# comcon_version_av.net
KiCad netlist of a schematic drawn in EAGLE
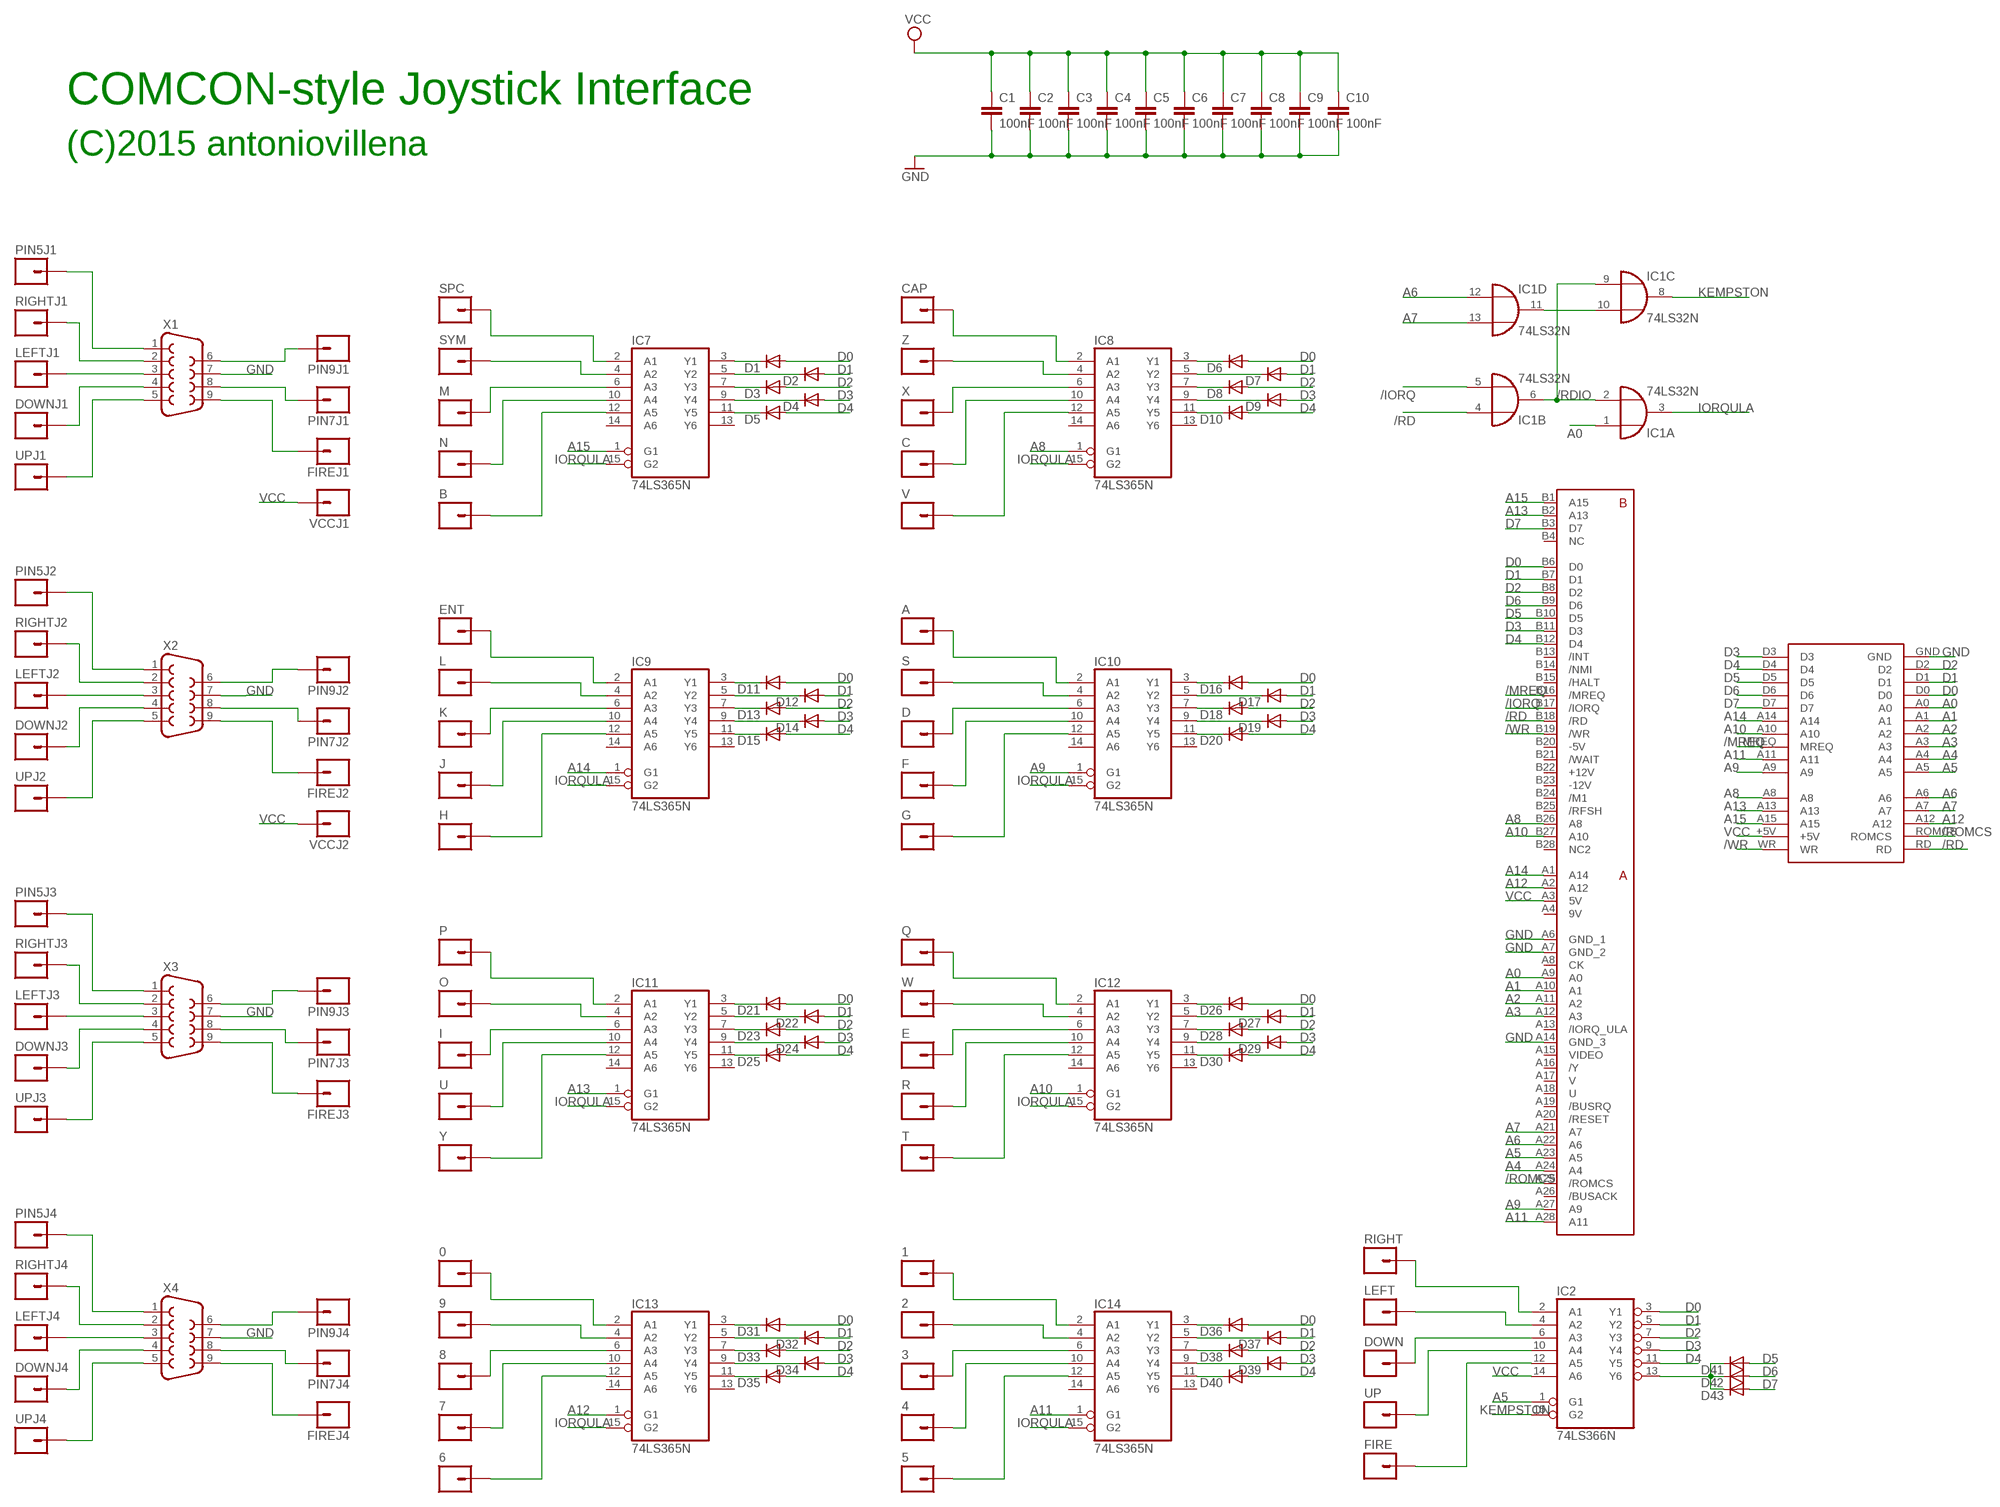
[diagram p0: schematic, sheet 1]

(export (version "E")
  (design (tool "Eeschema 10.0.6"))
  (components
    (comp (ref "0")
      (value "M01PTH")
      (footprint "eagle-import:1X01")
      (libsource (lib "eagle-import") (part "M01PTH"))
    )
    (comp (ref "1")
      (value "M01PTH")
      (footprint "eagle-import:1X01")
      (libsource (lib "eagle-import") (part "M01PTH"))
    )
    (comp (ref "2")
      (value "M01PTH")
      (footprint "eagle-import:1X01")
      (libsource (lib "eagle-import") (part "M01PTH"))
    )
    (comp (ref "3")
      (value "M01PTH")
      (footprint "eagle-import:1X01")
      (libsource (lib "eagle-import") (part "M01PTH"))
    )
    (comp (ref "4")
      (value "M01PTH")
      (footprint "eagle-import:1X01")
      (libsource (lib "eagle-import") (part "M01PTH"))
    )
    (comp (ref "5")
      (value "M01PTH")
      (footprint "eagle-import:1X01")
      (libsource (lib "eagle-import") (part "M01PTH"))
    )
    (comp (ref "6")
      (value "M01PTH")
      (footprint "eagle-import:1X01")
      (libsource (lib "eagle-import") (part "M01PTH"))
    )
    (comp (ref "7")
      (value "M01PTH")
      (footprint "eagle-import:1X01")
      (libsource (lib "eagle-import") (part "M01PTH"))
    )
    (comp (ref "8")
      (value "M01PTH")
      (footprint "eagle-import:1X01")
      (libsource (lib "eagle-import") (part "M01PTH"))
    )
    (comp (ref "9")
      (value "M01PTH")
      (footprint "eagle-import:1X01")
      (libsource (lib "eagle-import") (part "M01PTH"))
    )
    (comp (ref "A")
      (value "M01PTH")
      (footprint "eagle-import:1X01")
      (libsource (lib "eagle-import") (part "M01PTH"))
    )
    (comp (ref "B")
      (value "M01PTH")
      (footprint "eagle-import:1X01")
      (libsource (lib "eagle-import") (part "M01PTH"))
    )
    (comp (ref "C")
      (value "M01PTH")
      (footprint "eagle-import:1X01")
      (libsource (lib "eagle-import") (part "M01PTH"))
    )
    (comp (ref "C1")
      (value "100nF")
      (footprint "eagle-import:C050-025X075")
      (libsource (lib "eagle-import") (part "C-EU050-025X075"))
    )
    (comp (ref "C2")
      (value "100nF")
      (footprint "eagle-import:C050-025X075")
      (libsource (lib "eagle-import") (part "C-EU050-025X075"))
    )
    (comp (ref "C3")
      (value "100nF")
      (footprint "eagle-import:C050-025X075")
      (libsource (lib "eagle-import") (part "C-EU050-025X075"))
    )
    (comp (ref "C4")
      (value "100nF")
      (footprint "eagle-import:C050-025X075")
      (libsource (lib "eagle-import") (part "C-EU050-025X075"))
    )
    (comp (ref "C5")
      (value "100nF")
      (footprint "eagle-import:C050-025X075")
      (libsource (lib "eagle-import") (part "C-EU050-025X075"))
    )
    (comp (ref "C6")
      (value "100nF")
      (footprint "eagle-import:C050-025X075")
      (libsource (lib "eagle-import") (part "C-EU050-025X075"))
    )
    (comp (ref "C7")
      (value "100nF")
      (footprint "eagle-import:C050-025X075")
      (libsource (lib "eagle-import") (part "C-EU050-025X075"))
    )
    (comp (ref "C8")
      (value "100nF")
      (footprint "eagle-import:C050-025X075")
      (libsource (lib "eagle-import") (part "C-EU050-025X075"))
    )
    (comp (ref "C9")
      (value "100nF")
      (footprint "eagle-import:C050-025X075")
      (libsource (lib "eagle-import") (part "C-EU050-025X075"))
    )
    (comp (ref "C10")
      (value "100nF")
      (footprint "eagle-import:C050-025X075")
      (libsource (lib "eagle-import") (part "C-EU050-025X075"))
    )
    (comp (ref "CAP")
      (value "M01PTH")
      (footprint "eagle-import:1X01")
      (libsource (lib "eagle-import") (part "M01PTH"))
    )
    (comp (ref "D")
      (value "M01PTH")
      (footprint "eagle-import:1X01")
      (libsource (lib "eagle-import") (part "M01PTH"))
    )
    (comp (ref "D1")
      (value "1N4148DO35-7")
      (footprint "eagle-import:DO35-7")
      (libsource (lib "eagle-import") (part "1N4148DO35-7"))
    )
    (comp (ref "D2")
      (value "1N4148DO35-7")
      (footprint "eagle-import:DO35-7")
      (libsource (lib "eagle-import") (part "1N4148DO35-7"))
    )
    (comp (ref "D3")
      (value "1N4148DO35-7")
      (footprint "eagle-import:DO35-7")
      (libsource (lib "eagle-import") (part "1N4148DO35-7"))
    )
    (comp (ref "D4")
      (value "1N4148DO35-7")
      (footprint "eagle-import:DO35-7")
      (libsource (lib "eagle-import") (part "1N4148DO35-7"))
    )
    (comp (ref "D5")
      (value "1N4148DO35-7")
      (footprint "eagle-import:DO35-7")
      (libsource (lib "eagle-import") (part "1N4148DO35-7"))
    )
    (comp (ref "D6")
      (value "1N4148DO35-7")
      (footprint "eagle-import:DO35-7")
      (libsource (lib "eagle-import") (part "1N4148DO35-7"))
    )
    (comp (ref "D7")
      (value "1N4148DO35-7")
      (footprint "eagle-import:DO35-7")
      (libsource (lib "eagle-import") (part "1N4148DO35-7"))
    )
    (comp (ref "D8")
      (value "1N4148DO35-7")
      (footprint "eagle-import:DO35-7")
      (libsource (lib "eagle-import") (part "1N4148DO35-7"))
    )
    (comp (ref "D9")
      (value "1N4148DO35-7")
      (footprint "eagle-import:DO35-7")
      (libsource (lib "eagle-import") (part "1N4148DO35-7"))
    )
    (comp (ref "D10")
      (value "1N4148DO35-7")
      (footprint "eagle-import:DO35-7")
      (libsource (lib "eagle-import") (part "1N4148DO35-7"))
    )
    (comp (ref "D11")
      (value "1N4148DO35-7")
      (footprint "eagle-import:DO35-7")
      (libsource (lib "eagle-import") (part "1N4148DO35-7"))
    )
    (comp (ref "D12")
      (value "1N4148DO35-7")
      (footprint "eagle-import:DO35-7")
      (libsource (lib "eagle-import") (part "1N4148DO35-7"))
    )
    (comp (ref "D13")
      (value "1N4148DO35-7")
      (footprint "eagle-import:DO35-7")
      (libsource (lib "eagle-import") (part "1N4148DO35-7"))
    )
    (comp (ref "D14")
      (value "1N4148DO35-7")
      (footprint "eagle-import:DO35-7")
      (libsource (lib "eagle-import") (part "1N4148DO35-7"))
    )
    (comp (ref "D15")
      (value "1N4148DO35-7")
      (footprint "eagle-import:DO35-7")
      (libsource (lib "eagle-import") (part "1N4148DO35-7"))
    )
    (comp (ref "D16")
      (value "1N4148DO35-7")
      (footprint "eagle-import:DO35-7")
      (libsource (lib "eagle-import") (part "1N4148DO35-7"))
    )
    (comp (ref "D17")
      (value "1N4148DO35-7")
      (footprint "eagle-import:DO35-7")
      (libsource (lib "eagle-import") (part "1N4148DO35-7"))
    )
    (comp (ref "D18")
      (value "1N4148DO35-7")
      (footprint "eagle-import:DO35-7")
      (libsource (lib "eagle-import") (part "1N4148DO35-7"))
    )
    (comp (ref "D19")
      (value "1N4148DO35-7")
      (footprint "eagle-import:DO35-7")
      (libsource (lib "eagle-import") (part "1N4148DO35-7"))
    )
    (comp (ref "D20")
      (value "1N4148DO35-7")
      (footprint "eagle-import:DO35-7")
      (libsource (lib "eagle-import") (part "1N4148DO35-7"))
    )
    (comp (ref "D21")
      (value "1N4148DO35-7")
      (footprint "eagle-import:DO35-7")
      (libsource (lib "eagle-import") (part "1N4148DO35-7"))
    )
    (comp (ref "D22")
      (value "1N4148DO35-7")
      (footprint "eagle-import:DO35-7")
      (libsource (lib "eagle-import") (part "1N4148DO35-7"))
    )
    (comp (ref "D23")
      (value "1N4148DO35-7")
      (footprint "eagle-import:DO35-7")
      (libsource (lib "eagle-import") (part "1N4148DO35-7"))
    )
    (comp (ref "D24")
      (value "1N4148DO35-7")
      (footprint "eagle-import:DO35-7")
      (libsource (lib "eagle-import") (part "1N4148DO35-7"))
    )
    (comp (ref "D25")
      (value "1N4148DO35-7")
      (footprint "eagle-import:DO35-7")
      (libsource (lib "eagle-import") (part "1N4148DO35-7"))
    )
    (comp (ref "D26")
      (value "1N4148DO35-7")
      (footprint "eagle-import:DO35-7")
      (libsource (lib "eagle-import") (part "1N4148DO35-7"))
    )
    (comp (ref "D27")
      (value "1N4148DO35-7")
      (footprint "eagle-import:DO35-7")
      (libsource (lib "eagle-import") (part "1N4148DO35-7"))
    )
    (comp (ref "D28")
      (value "1N4148DO35-7")
      (footprint "eagle-import:DO35-7")
      (libsource (lib "eagle-import") (part "1N4148DO35-7"))
    )
    (comp (ref "D29")
      (value "1N4148DO35-7")
      (footprint "eagle-import:DO35-7")
      (libsource (lib "eagle-import") (part "1N4148DO35-7"))
    )
    (comp (ref "D30")
      (value "1N4148DO35-7")
      (footprint "eagle-import:DO35-7")
      (libsource (lib "eagle-import") (part "1N4148DO35-7"))
    )
    (comp (ref "D31")
      (value "1N4148DO35-7")
      (footprint "eagle-import:DO35-7")
      (libsource (lib "eagle-import") (part "1N4148DO35-7"))
    )
    (comp (ref "D32")
      (value "1N4148DO35-7")
      (footprint "eagle-import:DO35-7")
      (libsource (lib "eagle-import") (part "1N4148DO35-7"))
    )
    (comp (ref "D33")
      (value "1N4148DO35-7")
      (footprint "eagle-import:DO35-7")
      (libsource (lib "eagle-import") (part "1N4148DO35-7"))
    )
    (comp (ref "D34")
      (value "1N4148DO35-7")
      (footprint "eagle-import:DO35-7")
      (libsource (lib "eagle-import") (part "1N4148DO35-7"))
    )
    (comp (ref "D35")
      (value "1N4148DO35-7")
      (footprint "eagle-import:DO35-7")
      (libsource (lib "eagle-import") (part "1N4148DO35-7"))
    )
    (comp (ref "D36")
      (value "1N4148DO35-7")
      (footprint "eagle-import:DO35-7")
      (libsource (lib "eagle-import") (part "1N4148DO35-7"))
    )
    (comp (ref "D37")
      (value "1N4148DO35-7")
      (footprint "eagle-import:DO35-7")
      (libsource (lib "eagle-import") (part "1N4148DO35-7"))
    )
    (comp (ref "D38")
      (value "1N4148DO35-7")
      (footprint "eagle-import:DO35-7")
      (libsource (lib "eagle-import") (part "1N4148DO35-7"))
    )
    (comp (ref "D39")
      (value "1N4148DO35-7")
      (footprint "eagle-import:DO35-7")
      (libsource (lib "eagle-import") (part "1N4148DO35-7"))
    )
    (comp (ref "D40")
      (value "1N4148DO35-7")
      (footprint "eagle-import:DO35-7")
      (libsource (lib "eagle-import") (part "1N4148DO35-7"))
    )
    (comp (ref "D41")
      (value "1N4148DO35-10")
      (footprint "eagle-import:DO35-10")
      (libsource (lib "eagle-import") (part "1N4148DO35-10"))
    )
    (comp (ref "D42")
      (value "1N4148DO35-10")
      (footprint "eagle-import:DO35-10")
      (libsource (lib "eagle-import") (part "1N4148DO35-10"))
    )
    (comp (ref "D43")
      (value "1N4148DO35-7")
      (footprint "eagle-import:DO35-7")
      (libsource (lib "eagle-import") (part "1N4148DO35-7"))
    )
    (comp (ref "DOWN")
      (value "M01PTH")
      (footprint "eagle-import:1X01")
      (libsource (lib "eagle-import") (part "M01PTH"))
    )
    (comp (ref "DOWNJ1")
      (value "M01PTH")
      (footprint "eagle-import:1X01")
      (libsource (lib "eagle-import") (part "M01PTH"))
    )
    (comp (ref "DOWNJ2")
      (value "M01PTH")
      (footprint "eagle-import:1X01")
      (libsource (lib "eagle-import") (part "M01PTH"))
    )
    (comp (ref "DOWNJ3")
      (value "M01PTH")
      (footprint "eagle-import:1X01")
      (libsource (lib "eagle-import") (part "M01PTH"))
    )
    (comp (ref "DOWNJ4")
      (value "M01PTH")
      (footprint "eagle-import:1X01")
      (libsource (lib "eagle-import") (part "M01PTH"))
    )
    (comp (ref "E")
      (value "M01PTH")
      (footprint "eagle-import:1X01")
      (libsource (lib "eagle-import") (part "M01PTH"))
    )
    (comp (ref "ENT")
      (value "M01PTH")
      (footprint "eagle-import:1X01")
      (libsource (lib "eagle-import") (part "M01PTH"))
    )
    (comp (ref "F")
      (value "M01PTH")
      (footprint "eagle-import:1X01")
      (libsource (lib "eagle-import") (part "M01PTH"))
    )
    (comp (ref "FIRE")
      (value "M01PTH")
      (footprint "eagle-import:1X01")
      (libsource (lib "eagle-import") (part "M01PTH"))
    )
    (comp (ref "FIREJ1")
      (value "M01PTH")
      (footprint "eagle-import:1X01")
      (libsource (lib "eagle-import") (part "M01PTH"))
    )
    (comp (ref "FIREJ2")
      (value "M01PTH")
      (footprint "eagle-import:1X01")
      (libsource (lib "eagle-import") (part "M01PTH"))
    )
    (comp (ref "FIREJ3")
      (value "M01PTH")
      (footprint "eagle-import:1X01")
      (libsource (lib "eagle-import") (part "M01PTH"))
    )
    (comp (ref "FIREJ4")
      (value "M01PTH")
      (footprint "eagle-import:1X01")
      (libsource (lib "eagle-import") (part "M01PTH"))
    )
    (comp (ref "G")
      (value "M01PTH")
      (footprint "eagle-import:1X01")
      (libsource (lib "eagle-import") (part "M01PTH"))
    )
    (comp (ref "H")
      (value "M01PTH")
      (footprint "eagle-import:1X01")
      (libsource (lib "eagle-import") (part "M01PTH"))
    )
    (comp (ref "I")
      (value "M01PTH")
      (footprint "eagle-import:1X01")
      (libsource (lib "eagle-import") (part "M01PTH"))
    )
    (comp (ref "IC1")
      (value "74LS32N")
      (footprint "eagle-import:DIL14")
      (libsource (lib "eagle-import") (part "7432NLS"))
    )
    (comp (ref "IC2")
      (value "74LS366N")
      (footprint "eagle-import:DIL16")
      (libsource (lib "eagle-import") (part "74366NLS"))
    )
    (comp (ref "IC7")
      (value "74LS365N")
      (footprint "eagle-import:DIL16")
      (libsource (lib "eagle-import") (part "74365NHC"))
    )
    (comp (ref "IC8")
      (value "74LS365N")
      (footprint "eagle-import:DIL16")
      (libsource (lib "eagle-import") (part "74365NHC"))
    )
    (comp (ref "IC9")
      (value "74LS365N")
      (footprint "eagle-import:DIL16")
      (libsource (lib "eagle-import") (part "74365NHC"))
    )
    (comp (ref "IC10")
      (value "74LS365N")
      (footprint "eagle-import:DIL16")
      (libsource (lib "eagle-import") (part "74365NHC"))
    )
    (comp (ref "IC11")
      (value "74LS365N")
      (footprint "eagle-import:DIL16")
      (libsource (lib "eagle-import") (part "74365NHC"))
    )
    (comp (ref "IC12")
      (value "74LS365N")
      (footprint "eagle-import:DIL16")
      (libsource (lib "eagle-import") (part "74365NHC"))
    )
    (comp (ref "IC13")
      (value "74LS365N")
      (footprint "eagle-import:DIL16")
      (libsource (lib "eagle-import") (part "74365NHC"))
    )
    (comp (ref "IC14")
      (value "74LS365N")
      (footprint "eagle-import:DIL16")
      (libsource (lib "eagle-import") (part "74365NHC"))
    )
    (comp (ref "J")
      (value "M01PTH")
      (footprint "eagle-import:1X01")
      (libsource (lib "eagle-import") (part "M01PTH"))
    )
    (comp (ref "K")
      (value "M01PTH")
      (footprint "eagle-import:1X01")
      (libsource (lib "eagle-import") (part "M01PTH"))
    )
    (comp (ref "L")
      (value "M01PTH")
      (footprint "eagle-import:1X01")
      (libsource (lib "eagle-import") (part "M01PTH"))
    )
    (comp (ref "LEFT")
      (value "M01PTH")
      (footprint "eagle-import:1X01")
      (libsource (lib "eagle-import") (part "M01PTH"))
    )
    (comp (ref "LEFTJ1")
      (value "M01PTH")
      (footprint "eagle-import:1X01")
      (libsource (lib "eagle-import") (part "M01PTH"))
    )
    (comp (ref "LEFTJ2")
      (value "M01PTH")
      (footprint "eagle-import:1X01")
      (libsource (lib "eagle-import") (part "M01PTH"))
    )
    (comp (ref "LEFTJ3")
      (value "M01PTH")
      (footprint "eagle-import:1X01")
      (libsource (lib "eagle-import") (part "M01PTH"))
    )
    (comp (ref "LEFTJ4")
      (value "M01PTH")
      (footprint "eagle-import:1X01")
      (libsource (lib "eagle-import") (part "M01PTH"))
    )
    (comp (ref "M")
      (value "M01PTH")
      (footprint "eagle-import:1X01")
      (libsource (lib "eagle-import") (part "M01PTH"))
    )
    (comp (ref "N")
      (value "M01PTH")
      (footprint "eagle-import:1X01")
      (libsource (lib "eagle-import") (part "M01PTH"))
    )
    (comp (ref "O")
      (value "M01PTH")
      (footprint "eagle-import:1X01")
      (libsource (lib "eagle-import") (part "M01PTH"))
    )
    (comp (ref "P")
      (value "M01PTH")
      (footprint "eagle-import:1X01")
      (libsource (lib "eagle-import") (part "M01PTH"))
    )
    (comp (ref "PIN5J1")
      (value "M01PTH")
      (footprint "eagle-import:1X01")
      (libsource (lib "eagle-import") (part "M01PTH"))
    )
    (comp (ref "PIN5J2")
      (value "M01PTH")
      (footprint "eagle-import:1X01")
      (libsource (lib "eagle-import") (part "M01PTH"))
    )
    (comp (ref "PIN5J3")
      (value "M01PTH")
      (footprint "eagle-import:1X01")
      (libsource (lib "eagle-import") (part "M01PTH"))
    )
    (comp (ref "PIN5J4")
      (value "M01PTH")
      (footprint "eagle-import:1X01")
      (libsource (lib "eagle-import") (part "M01PTH"))
    )
    (comp (ref "PIN7J1")
      (value "M01PTH")
      (footprint "eagle-import:1X01")
      (libsource (lib "eagle-import") (part "M01PTH"))
    )
    (comp (ref "PIN7J2")
      (value "M01PTH")
      (footprint "eagle-import:1X01")
      (libsource (lib "eagle-import") (part "M01PTH"))
    )
    (comp (ref "PIN7J3")
      (value "M01PTH")
      (footprint "eagle-import:1X01")
      (libsource (lib "eagle-import") (part "M01PTH"))
    )
    (comp (ref "PIN7J4")
      (value "M01PTH")
      (footprint "eagle-import:1X01")
      (libsource (lib "eagle-import") (part "M01PTH"))
    )
    (comp (ref "PIN9J1")
      (value "M01PTH")
      (footprint "eagle-import:1X01")
      (libsource (lib "eagle-import") (part "M01PTH"))
    )
    (comp (ref "PIN9J2")
      (value "M01PTH")
      (footprint "eagle-import:1X01")
      (libsource (lib "eagle-import") (part "M01PTH"))
    )
    (comp (ref "PIN9J3")
      (value "M01PTH")
      (footprint "eagle-import:1X01")
      (libsource (lib "eagle-import") (part "M01PTH"))
    )
    (comp (ref "PIN9J4")
      (value "M01PTH")
      (footprint "eagle-import:1X01")
      (libsource (lib "eagle-import") (part "M01PTH"))
    )
    (comp (ref "Q")
      (value "M01PTH")
      (footprint "eagle-import:1X01")
      (libsource (lib "eagle-import") (part "M01PTH"))
    )
    (comp (ref "R")
      (value "M01PTH")
      (footprint "eagle-import:1X01")
      (libsource (lib "eagle-import") (part "M01PTH"))
    )
    (comp (ref "RIGHT")
      (value "M01PTH")
      (footprint "eagle-import:1X01")
      (libsource (lib "eagle-import") (part "M01PTH"))
    )
    (comp (ref "RIGHTJ1")
      (value "M01PTH")
      (footprint "eagle-import:1X01")
      (libsource (lib "eagle-import") (part "M01PTH"))
    )
    (comp (ref "RIGHTJ2")
      (value "M01PTH")
      (footprint "eagle-import:1X01")
      (libsource (lib "eagle-import") (part "M01PTH"))
    )
    (comp (ref "RIGHTJ3")
      (value "M01PTH")
      (footprint "eagle-import:1X01")
      (libsource (lib "eagle-import") (part "M01PTH"))
    )
    (comp (ref "RIGHTJ4")
      (value "M01PTH")
      (footprint "eagle-import:1X01")
      (libsource (lib "eagle-import") (part "M01PTH"))
    )
    (comp (ref "S")
      (value "M01PTH")
      (footprint "eagle-import:1X01")
      (libsource (lib "eagle-import") (part "M01PTH"))
    )
    (comp (ref "SPC")
      (value "M01PTH")
      (footprint "eagle-import:1X01")
      (libsource (lib "eagle-import") (part "M01PTH"))
    )
    (comp (ref "SYM")
      (value "M01PTH")
      (footprint "eagle-import:1X01")
      (libsource (lib "eagle-import") (part "M01PTH"))
    )
    (comp (ref "T")
      (value "M01PTH")
      (footprint "eagle-import:1X01")
      (libsource (lib "eagle-import") (part "M01PTH"))
    )
    (comp (ref "U")
      (value "M01PTH")
      (footprint "eagle-import:1X01")
      (libsource (lib "eagle-import") (part "M01PTH"))
    )
    (comp (ref "U$1")
      (value "ZX_CARTRIDGE")
      (footprint "eagle-import:ZX_CARTRIDGE")
      (libsource (lib "eagle-import") (part "ZX_CARTRIDGE"))
    )
    (comp (ref "U$3")
      (value "ZXSP_ED2X28_SPE")
      (footprint "eagle-import:2X28_SPE")
      (libsource (lib "eagle-import") (part "ZXSP_ED2X28_SPE"))
    )
    (comp (ref "UP")
      (value "M01PTH")
      (footprint "eagle-import:1X01")
      (libsource (lib "eagle-import") (part "M01PTH"))
    )
    (comp (ref "UPJ1")
      (value "M01PTH")
      (footprint "eagle-import:1X01")
      (libsource (lib "eagle-import") (part "M01PTH"))
    )
    (comp (ref "UPJ2")
      (value "M01PTH")
      (footprint "eagle-import:1X01")
      (libsource (lib "eagle-import") (part "M01PTH"))
    )
    (comp (ref "UPJ3")
      (value "M01PTH")
      (footprint "eagle-import:1X01")
      (libsource (lib "eagle-import") (part "M01PTH"))
    )
    (comp (ref "UPJ4")
      (value "M01PTH")
      (footprint "eagle-import:1X01")
      (libsource (lib "eagle-import") (part "M01PTH"))
    )
    (comp (ref "V")
      (value "M01PTH")
      (footprint "eagle-import:1X01")
      (libsource (lib "eagle-import") (part "M01PTH"))
    )
    (comp (ref "VCCJ1")
      (value "M01PTH")
      (footprint "eagle-import:1X01")
      (libsource (lib "eagle-import") (part "M01PTH"))
    )
    (comp (ref "VCCJ2")
      (value "M01PTH")
      (footprint "eagle-import:1X01")
      (libsource (lib "eagle-import") (part "M01PTH"))
    )
    (comp (ref "W")
      (value "M01PTH")
      (footprint "eagle-import:1X01")
      (libsource (lib "eagle-import") (part "M01PTH"))
    )
    (comp (ref "X")
      (value "M01PTH")
      (footprint "eagle-import:1X01")
      (libsource (lib "eagle-import") (part "M01PTH"))
    )
    (comp (ref "X1")
      (value "F09D")
      (footprint "eagle-import:F09D")
      (libsource (lib "eagle-import") (part "F09D"))
    )
    (comp (ref "X2")
      (value "F09D")
      (footprint "eagle-import:F09D")
      (libsource (lib "eagle-import") (part "F09D"))
    )
    (comp (ref "X3")
      (value "F09D")
      (footprint "eagle-import:F09D")
      (libsource (lib "eagle-import") (part "F09D"))
    )
    (comp (ref "X4")
      (value "F09D")
      (footprint "eagle-import:F09D")
      (libsource (lib "eagle-import") (part "F09D"))
    )
    (comp (ref "Y")
      (value "M01PTH")
      (footprint "eagle-import:1X01")
      (libsource (lib "eagle-import") (part "M01PTH"))
    )
    (comp (ref "Z")
      (value "M01PTH")
      (footprint "eagle-import:1X01")
      (libsource (lib "eagle-import") (part "M01PTH"))
    )
  )
  (nets
    (net (code "1") (name "/+12V") (class "Default")
      (node (ref "U$3") (pin "B22") (pinfunction "+12V_B22") (pintype "power_in"))
    )
    (net (code "2") (name "/-5V") (class "Default")
      (node (ref "U$3") (pin "B20") (pinfunction "-5V_B20") (pintype "power_in"))
    )
    (net (code "3") (name "/-12V") (class "Default")
      (node (ref "U$3") (pin "B23") (pinfunction "-12V_B23") (pintype "power_in"))
    )
    (net (code "4") (name "/9V") (class "Default")
      (node (ref "U$3") (pin "A4") (pinfunction "9V_A4") (pintype "power_in"))
    )
    (net (code "5") (name "/A0") (class "Default")
      (node (ref "IC1") (pin "1") (pinfunction "I0_1") (pintype "input"))
      (node (ref "U$1") (pin "A0") (pinfunction "A0_A0") (pintype "bidirectional"))
      (node (ref "U$3") (pin "A9") (pinfunction "A0_A9") (pintype "bidirectional"))
    )
    (net (code "6") (name "/A1") (class "Default")
      (node (ref "U$1") (pin "A1") (pinfunction "A1_A1") (pintype "bidirectional"))
      (node (ref "U$3") (pin "A10") (pinfunction "A1_A10") (pintype "bidirectional"))
    )
    (net (code "7") (name "/A2") (class "Default")
      (node (ref "U$1") (pin "A2") (pinfunction "A2_A2") (pintype "bidirectional"))
      (node (ref "U$3") (pin "A11") (pinfunction "A2_A11") (pintype "bidirectional"))
    )
    (net (code "8") (name "/A3") (class "Default")
      (node (ref "U$1") (pin "A3") (pinfunction "A3_A3") (pintype "bidirectional"))
      (node (ref "U$3") (pin "A12") (pinfunction "A3_A12") (pintype "bidirectional"))
    )
    (net (code "9") (name "/A4") (class "Default")
      (node (ref "U$1") (pin "A4") (pinfunction "A4_A4") (pintype "bidirectional"))
      (node (ref "U$3") (pin "A24") (pinfunction "A4_A24") (pintype "bidirectional"))
    )
    (net (code "10") (name "/A5") (class "Default")
      (node (ref "IC2") (pin "1") (pinfunction "G1_1") (pintype "input"))
      (node (ref "U$1") (pin "A5") (pinfunction "A5_A5") (pintype "bidirectional"))
      (node (ref "U$3") (pin "A23") (pinfunction "A5_A23") (pintype "bidirectional"))
    )
    (net (code "11") (name "/A6") (class "Default")
      (node (ref "IC1") (pin "12") (pinfunction "I0_12") (pintype "input"))
      (node (ref "U$1") (pin "A6") (pinfunction "A6_A6") (pintype "bidirectional"))
      (node (ref "U$3") (pin "A22") (pinfunction "A6_A22") (pintype "bidirectional"))
    )
    (net (code "12") (name "/A7") (class "Default")
      (node (ref "IC1") (pin "13") (pinfunction "I1_13") (pintype "input"))
      (node (ref "U$1") (pin "A7") (pinfunction "A7_A7") (pintype "bidirectional"))
      (node (ref "U$3") (pin "A21") (pinfunction "A7_A21") (pintype "bidirectional"))
    )
    (net (code "13") (name "/A8") (class "Default")
      (node (ref "IC8") (pin "1") (pinfunction "G1_1") (pintype "input"))
      (node (ref "U$1") (pin "A8") (pinfunction "A8_A8") (pintype "bidirectional"))
      (node (ref "U$3") (pin "B26") (pinfunction "A8_B26") (pintype "bidirectional"))
    )
    (net (code "14") (name "/A9") (class "Default")
      (node (ref "IC10") (pin "1") (pinfunction "G1_1") (pintype "input"))
      (node (ref "U$1") (pin "A9") (pinfunction "A9_A9") (pintype "bidirectional"))
      (node (ref "U$3") (pin "A27") (pinfunction "A9_A27") (pintype "bidirectional"))
    )
    (net (code "15") (name "/A10") (class "Default")
      (node (ref "IC12") (pin "1") (pinfunction "G1_1") (pintype "input"))
      (node (ref "U$1") (pin "A10") (pinfunction "A10_A10") (pintype "bidirectional"))
      (node (ref "U$3") (pin "B27") (pinfunction "A10_B27") (pintype "bidirectional"))
    )
    (net (code "16") (name "/A11") (class "Default")
      (node (ref "IC14") (pin "1") (pinfunction "G1_1") (pintype "input"))
      (node (ref "U$1") (pin "A11") (pinfunction "A11_A11") (pintype "bidirectional"))
      (node (ref "U$3") (pin "A28") (pinfunction "A11_A28") (pintype "bidirectional"))
    )
    (net (code "17") (name "/A12") (class "Default")
      (node (ref "IC13") (pin "1") (pinfunction "G1_1") (pintype "input"))
      (node (ref "U$1") (pin "A12") (pinfunction "A12_A12") (pintype "bidirectional"))
      (node (ref "U$3") (pin "A2") (pinfunction "A12_A2") (pintype "bidirectional"))
    )
    (net (code "18") (name "/A13") (class "Default")
      (node (ref "IC11") (pin "1") (pinfunction "G1_1") (pintype "input"))
      (node (ref "U$1") (pin "A13") (pinfunction "A13_A13") (pintype "bidirectional"))
      (node (ref "U$3") (pin "B2") (pinfunction "A13_B2") (pintype "bidirectional"))
    )
    (net (code "19") (name "/A14") (class "Default")
      (node (ref "IC9") (pin "1") (pinfunction "G1_1") (pintype "input"))
      (node (ref "U$1") (pin "A14") (pinfunction "A14_A14") (pintype "bidirectional"))
      (node (ref "U$3") (pin "A1") (pinfunction "A14_A1") (pintype "bidirectional"))
    )
    (net (code "20") (name "/A15") (class "Default")
      (node (ref "IC7") (pin "1") (pinfunction "G1_1") (pintype "input"))
      (node (ref "U$1") (pin "A15") (pinfunction "A15_A15") (pintype "bidirectional"))
      (node (ref "U$3") (pin "B1") (pinfunction "A15_B1") (pintype "bidirectional"))
    )
    (net (code "21") (name "/D0") (class "Default")
      (node (ref "D1") (pin "A") (pinfunction "A_A") (pintype "passive"))
      (node (ref "D11") (pin "A") (pinfunction "A_A") (pintype "passive"))
      (node (ref "D16") (pin "A") (pinfunction "A_A") (pintype "passive"))
      (node (ref "D21") (pin "A") (pinfunction "A_A") (pintype "passive"))
      (node (ref "D26") (pin "A") (pinfunction "A_A") (pintype "passive"))
      (node (ref "D31") (pin "A") (pinfunction "A_A") (pintype "passive"))
      (node (ref "D36") (pin "A") (pinfunction "A_A") (pintype "passive"))
      (node (ref "D6") (pin "A") (pinfunction "A_A") (pintype "passive"))
      (node (ref "IC2") (pin "3") (pinfunction "Y1_3") (pintype "tri_state"))
      (node (ref "U$1") (pin "D0") (pinfunction "D0_D0") (pintype "bidirectional"))
      (node (ref "U$3") (pin "B6") (pinfunction "D0_B6") (pintype "bidirectional"))
    )
    (net (code "22") (name "/D1") (class "Default")
      (node (ref "D12") (pin "A") (pinfunction "A_A") (pintype "passive"))
      (node (ref "D17") (pin "A") (pinfunction "A_A") (pintype "passive"))
      (node (ref "D2") (pin "A") (pinfunction "A_A") (pintype "passive"))
      (node (ref "D22") (pin "A") (pinfunction "A_A") (pintype "passive"))
      (node (ref "D27") (pin "A") (pinfunction "A_A") (pintype "passive"))
      (node (ref "D32") (pin "A") (pinfunction "A_A") (pintype "passive"))
      (node (ref "D37") (pin "A") (pinfunction "A_A") (pintype "passive"))
      (node (ref "D7") (pin "A") (pinfunction "A_A") (pintype "passive"))
      (node (ref "IC2") (pin "5") (pinfunction "Y2_5") (pintype "tri_state"))
      (node (ref "U$1") (pin "D1") (pinfunction "D1_D1") (pintype "bidirectional"))
      (node (ref "U$3") (pin "B7") (pinfunction "D1_B7") (pintype "bidirectional"))
    )
    (net (code "23") (name "/D2") (class "Default")
      (node (ref "D13") (pin "A") (pinfunction "A_A") (pintype "passive"))
      (node (ref "D18") (pin "A") (pinfunction "A_A") (pintype "passive"))
      (node (ref "D23") (pin "A") (pinfunction "A_A") (pintype "passive"))
      (node (ref "D28") (pin "A") (pinfunction "A_A") (pintype "passive"))
      (node (ref "D3") (pin "A") (pinfunction "A_A") (pintype "passive"))
      (node (ref "D33") (pin "A") (pinfunction "A_A") (pintype "passive"))
      (node (ref "D38") (pin "A") (pinfunction "A_A") (pintype "passive"))
      (node (ref "D8") (pin "A") (pinfunction "A_A") (pintype "passive"))
      (node (ref "IC2") (pin "7") (pinfunction "Y3_7") (pintype "tri_state"))
      (node (ref "U$1") (pin "D2") (pinfunction "D2_D2") (pintype "bidirectional"))
      (node (ref "U$3") (pin "B8") (pinfunction "D2_B8") (pintype "bidirectional"))
    )
    (net (code "24") (name "/D3") (class "Default")
      (node (ref "D14") (pin "A") (pinfunction "A_A") (pintype "passive"))
      (node (ref "D19") (pin "A") (pinfunction "A_A") (pintype "passive"))
      (node (ref "D24") (pin "A") (pinfunction "A_A") (pintype "passive"))
      (node (ref "D29") (pin "A") (pinfunction "A_A") (pintype "passive"))
      (node (ref "D34") (pin "A") (pinfunction "A_A") (pintype "passive"))
      (node (ref "D39") (pin "A") (pinfunction "A_A") (pintype "passive"))
      (node (ref "D4") (pin "A") (pinfunction "A_A") (pintype "passive"))
      (node (ref "D9") (pin "A") (pinfunction "A_A") (pintype "passive"))
      (node (ref "IC2") (pin "9") (pinfunction "Y4_9") (pintype "tri_state"))
      (node (ref "U$1") (pin "D3") (pinfunction "D3_D3") (pintype "bidirectional"))
      (node (ref "U$3") (pin "B11") (pinfunction "D3_B11") (pintype "bidirectional"))
    )
    (net (code "25") (name "/D4") (class "Default")
      (node (ref "D10") (pin "A") (pinfunction "A_A") (pintype "passive"))
      (node (ref "D15") (pin "A") (pinfunction "A_A") (pintype "passive"))
      (node (ref "D20") (pin "A") (pinfunction "A_A") (pintype "passive"))
      (node (ref "D25") (pin "A") (pinfunction "A_A") (pintype "passive"))
      (node (ref "D30") (pin "A") (pinfunction "A_A") (pintype "passive"))
      (node (ref "D35") (pin "A") (pinfunction "A_A") (pintype "passive"))
      (node (ref "D40") (pin "A") (pinfunction "A_A") (pintype "passive"))
      (node (ref "D5") (pin "A") (pinfunction "A_A") (pintype "passive"))
      (node (ref "IC2") (pin "11") (pinfunction "Y5_11") (pintype "tri_state"))
      (node (ref "U$1") (pin "D4") (pinfunction "D4_D4") (pintype "bidirectional"))
      (node (ref "U$3") (pin "B12") (pinfunction "D4_B12") (pintype "bidirectional"))
    )
    (net (code "26") (name "/D5") (class "Default")
      (node (ref "D41") (pin "A") (pinfunction "A_A") (pintype "passive"))
      (node (ref "U$1") (pin "D5") (pinfunction "D5_D5") (pintype "bidirectional"))
      (node (ref "U$3") (pin "B10") (pinfunction "D5_B10") (pintype "bidirectional"))
    )
    (net (code "27") (name "/D6") (class "Default")
      (node (ref "D42") (pin "A") (pinfunction "A_A") (pintype "passive"))
      (node (ref "U$1") (pin "D6") (pinfunction "D6_D6") (pintype "bidirectional"))
      (node (ref "U$3") (pin "B9") (pinfunction "D6_B9") (pintype "bidirectional"))
    )
    (net (code "28") (name "/D7") (class "Default")
      (node (ref "D43") (pin "A") (pinfunction "A_A") (pintype "passive"))
      (node (ref "U$1") (pin "D7") (pinfunction "D7_D7") (pintype "bidirectional"))
      (node (ref "U$3") (pin "B3") (pinfunction "D7_B3") (pintype "bidirectional"))
    )
    (net (code "29") (name "/IORQULA") (class "Default")
      (node (ref "IC1") (pin "3") (pinfunction "O_3") (pintype "output"))
      (node (ref "IC10") (pin "15") (pinfunction "G2_15") (pintype "input"))
      (node (ref "IC11") (pin "15") (pinfunction "G2_15") (pintype "input"))
      (node (ref "IC12") (pin "15") (pinfunction "G2_15") (pintype "input"))
      (node (ref "IC13") (pin "15") (pinfunction "G2_15") (pintype "input"))
      (node (ref "IC14") (pin "15") (pinfunction "G2_15") (pintype "input"))
      (node (ref "IC7") (pin "15") (pinfunction "G2_15") (pintype "input"))
      (node (ref "IC8") (pin "15") (pinfunction "G2_15") (pintype "input"))
      (node (ref "IC9") (pin "15") (pinfunction "G2_15") (pintype "input"))
    )
    (net (code "30") (name "/KEMPSTON") (class "Default")
      (node (ref "IC1") (pin "8") (pinfunction "O_8") (pintype "output"))
      (node (ref "IC2") (pin "15") (pinfunction "G2_15") (pintype "input"))
    )
    (net (code "31") (name "/{slash}IORQ") (class "Default")
      (node (ref "IC1") (pin "5") (pinfunction "I1_5") (pintype "input"))
      (node (ref "U$3") (pin "B17") (pinfunction "/IORQ_B17") (pintype "bidirectional"))
    )
    (net (code "32") (name "/{slash}MREQ") (class "Default")
      (node (ref "U$1") (pin "MREQ") (pinfunction "MREQ_MREQ") (pintype "bidirectional"))
      (node (ref "U$3") (pin "B16") (pinfunction "/MREQ_B16") (pintype "bidirectional"))
    )
    (net (code "33") (name "/{slash}RD") (class "Default")
      (node (ref "IC1") (pin "4") (pinfunction "I0_4") (pintype "input"))
      (node (ref "U$1") (pin "RD") (pinfunction "RD_RD") (pintype "bidirectional"))
      (node (ref "U$3") (pin "B18") (pinfunction "/RD_B18") (pintype "bidirectional"))
    )
    (net (code "34") (name "/{slash}RDIO") (class "Default")
      (node (ref "IC1") (pin "2") (pinfunction "I1_2") (pintype "input"))
      (node (ref "IC1") (pin "6") (pinfunction "O_6") (pintype "output"))
      (node (ref "IC1") (pin "9") (pinfunction "I0_9") (pintype "input"))
    )
    (net (code "35") (name "/{slash}ROMCS") (class "Default")
      (node (ref "U$1") (pin "ROMCS") (pinfunction "ROMCS_ROMCS") (pintype "bidirectional"))
      (node (ref "U$3") (pin "A25") (pinfunction "/ROMCS_A25") (pintype "bidirectional"))
    )
    (net (code "36") (name "/{slash}WR") (class "Default")
      (node (ref "U$1") (pin "WR") (pinfunction "WR_WR") (pintype "bidirectional"))
      (node (ref "U$3") (pin "B19") (pinfunction "/WR_B19") (pintype "bidirectional"))
    )
    (net (code "37") (name "GND") (class "Default")
      (node (ref "C1") (pin "2") (pinfunction "2_2") (pintype "passive"))
      (node (ref "C10") (pin "2") (pinfunction "2_2") (pintype "passive"))
      (node (ref "C2") (pin "2") (pinfunction "2_2") (pintype "passive"))
      (node (ref "C3") (pin "2") (pinfunction "2_2") (pintype "passive"))
      (node (ref "C4") (pin "2") (pinfunction "2_2") (pintype "passive"))
      (node (ref "C5") (pin "2") (pinfunction "2_2") (pintype "passive"))
      (node (ref "C6") (pin "2") (pinfunction "2_2") (pintype "passive"))
      (node (ref "C7") (pin "2") (pinfunction "2_2") (pintype "passive"))
      (node (ref "C8") (pin "2") (pinfunction "2_2") (pintype "passive"))
      (node (ref "C9") (pin "2") (pinfunction "2_2") (pintype "passive"))
      (node (ref "U$1") (pin "GND") (pinfunction "GND_GND") (pintype "bidirectional"))
      (node (ref "U$3") (pin "A14") (pinfunction "GND_3_A14") (pintype "power_in"))
      (node (ref "U$3") (pin "A6") (pinfunction "GND_1_A6") (pintype "power_in"))
      (node (ref "U$3") (pin "A7") (pinfunction "GND_2_A7") (pintype "power_in"))
      (node (ref "X1") (pin "7") (pinfunction "7_7") (pintype "passive"))
      (node (ref "X2") (pin "7") (pinfunction "7_7") (pintype "passive"))
      (node (ref "X3") (pin "7") (pinfunction "7_7") (pintype "passive"))
      (node (ref "X4") (pin "7") (pinfunction "7_7") (pintype "passive"))
    )
    (net (code "38") (name "Net-(DOWNJ1-Pad1)") (class "Default")
      (node (ref "DOWNJ1") (pin "1") (pinfunction "1_1") (pintype "passive"))
      (node (ref "X1") (pin "4") (pinfunction "4_4") (pintype "passive"))
    )
    (net (code "39") (name "Net-(DOWNJ2-Pad1)") (class "Default")
      (node (ref "DOWNJ2") (pin "1") (pinfunction "1_1") (pintype "passive"))
      (node (ref "X2") (pin "4") (pinfunction "4_4") (pintype "passive"))
    )
    (net (code "40") (name "Net-(DOWNJ3-Pad1)") (class "Default")
      (node (ref "DOWNJ3") (pin "1") (pinfunction "1_1") (pintype "passive"))
      (node (ref "X3") (pin "4") (pinfunction "4_4") (pintype "passive"))
    )
    (net (code "41") (name "Net-(DOWNJ4-Pad1)") (class "Default")
      (node (ref "DOWNJ4") (pin "1") (pinfunction "1_1") (pintype "passive"))
      (node (ref "X4") (pin "4") (pinfunction "4_4") (pintype "passive"))
    )
    (net (code "42") (name "Net-(FIREJ1-Pad1)") (class "Default")
      (node (ref "FIREJ1") (pin "1") (pinfunction "1_1") (pintype "passive"))
      (node (ref "X1") (pin "9") (pinfunction "9_9") (pintype "passive"))
    )
    (net (code "43") (name "Net-(FIREJ2-Pad1)") (class "Default")
      (node (ref "FIREJ2") (pin "1") (pinfunction "1_1") (pintype "passive"))
      (node (ref "X2") (pin "9") (pinfunction "9_9") (pintype "passive"))
    )
    (net (code "44") (name "Net-(FIREJ3-Pad1)") (class "Default")
      (node (ref "FIREJ3") (pin "1") (pinfunction "1_1") (pintype "passive"))
      (node (ref "X3") (pin "9") (pinfunction "9_9") (pintype "passive"))
    )
    (net (code "45") (name "Net-(FIREJ4-Pad1)") (class "Default")
      (node (ref "FIREJ4") (pin "1") (pinfunction "1_1") (pintype "passive"))
      (node (ref "X4") (pin "9") (pinfunction "9_9") (pintype "passive"))
    )
    (net (code "46") (name "Net-(IC1C-I1)") (class "Default")
      (node (ref "IC1") (pin "10") (pinfunction "I1_10") (pintype "input"))
      (node (ref "IC1") (pin "11") (pinfunction "O_11") (pintype "output"))
    )
    (net (code "47") (name "Net-(IC2A-A1)") (class "Default")
      (node (ref "IC2") (pin "2") (pinfunction "A1_2") (pintype "input"))
      (node (ref "RIGHT") (pin "1") (pinfunction "1_1") (pintype "passive"))
    )
    (net (code "48") (name "Net-(IC2A-A2)") (class "Default")
      (node (ref "IC2") (pin "4") (pinfunction "A2_4") (pintype "input"))
      (node (ref "LEFT") (pin "1") (pinfunction "1_1") (pintype "passive"))
    )
    (net (code "49") (name "Net-(IC2A-A3)") (class "Default")
      (node (ref "DOWN") (pin "1") (pinfunction "1_1") (pintype "passive"))
      (node (ref "IC2") (pin "6") (pinfunction "A3_6") (pintype "input"))
    )
    (net (code "50") (name "Net-(IC2A-A4)") (class "Default")
      (node (ref "IC2") (pin "10") (pinfunction "A4_10") (pintype "input"))
      (node (ref "UP") (pin "1") (pinfunction "1_1") (pintype "passive"))
    )
    (net (code "51") (name "Net-(IC2A-A5)") (class "Default")
      (node (ref "FIRE") (pin "1") (pinfunction "1_1") (pintype "passive"))
      (node (ref "IC2") (pin "12") (pinfunction "A5_12") (pintype "input"))
    )
    (net (code "52") (name "Net-(IC2A-Y6)") (class "Default")
      (node (ref "D41") (pin "C") (pinfunction "C_C") (pintype "passive"))
      (node (ref "D42") (pin "C") (pinfunction "C_C") (pintype "passive"))
      (node (ref "D43") (pin "C") (pinfunction "C_C") (pintype "passive"))
      (node (ref "IC2") (pin "13") (pinfunction "Y6_13") (pintype "tri_state"))
    )
    (net (code "53") (name "Net-(IC7A-A1)") (class "Default")
      (node (ref "IC7") (pin "2") (pinfunction "A1_2") (pintype "input"))
      (node (ref "SPC") (pin "1") (pinfunction "1_1") (pintype "passive"))
    )
    (net (code "54") (name "Net-(IC7A-A2)") (class "Default")
      (node (ref "IC7") (pin "4") (pinfunction "A2_4") (pintype "input"))
      (node (ref "SYM") (pin "1") (pinfunction "1_1") (pintype "passive"))
    )
    (net (code "55") (name "Net-(IC7A-A3)") (class "Default")
      (node (ref "IC7") (pin "6") (pinfunction "A3_6") (pintype "input"))
      (node (ref "M") (pin "1") (pinfunction "1_1") (pintype "passive"))
    )
    (net (code "56") (name "Net-(IC7A-A4)") (class "Default")
      (node (ref "IC7") (pin "10") (pinfunction "A4_10") (pintype "input"))
      (node (ref "N") (pin "1") (pinfunction "1_1") (pintype "passive"))
    )
    (net (code "57") (name "Net-(IC7A-A5)") (class "Default")
      (node (ref "B") (pin "1") (pinfunction "1_1") (pintype "passive"))
      (node (ref "IC7") (pin "12") (pinfunction "A5_12") (pintype "input"))
    )
    (net (code "58") (name "Net-(IC7A-Y1)") (class "Default")
      (node (ref "D1") (pin "C") (pinfunction "C_C") (pintype "passive"))
      (node (ref "IC7") (pin "3") (pinfunction "Y1_3") (pintype "tri_state"))
    )
    (net (code "59") (name "Net-(IC7A-Y2)") (class "Default")
      (node (ref "D2") (pin "C") (pinfunction "C_C") (pintype "passive"))
      (node (ref "IC7") (pin "5") (pinfunction "Y2_5") (pintype "tri_state"))
    )
    (net (code "60") (name "Net-(IC7A-Y3)") (class "Default")
      (node (ref "D3") (pin "C") (pinfunction "C_C") (pintype "passive"))
      (node (ref "IC7") (pin "7") (pinfunction "Y3_7") (pintype "tri_state"))
    )
    (net (code "61") (name "Net-(IC7A-Y4)") (class "Default")
      (node (ref "D4") (pin "C") (pinfunction "C_C") (pintype "passive"))
      (node (ref "IC7") (pin "9") (pinfunction "Y4_9") (pintype "tri_state"))
    )
    (net (code "62") (name "Net-(IC7A-Y5)") (class "Default")
      (node (ref "D5") (pin "C") (pinfunction "C_C") (pintype "passive"))
      (node (ref "IC7") (pin "11") (pinfunction "Y5_11") (pintype "tri_state"))
    )
    (net (code "63") (name "Net-(IC8A-A1)") (class "Default")
      (node (ref "CAP") (pin "1") (pinfunction "1_1") (pintype "passive"))
      (node (ref "IC8") (pin "2") (pinfunction "A1_2") (pintype "input"))
    )
    (net (code "64") (name "Net-(IC8A-A2)") (class "Default")
      (node (ref "IC8") (pin "4") (pinfunction "A2_4") (pintype "input"))
      (node (ref "Z") (pin "1") (pinfunction "1_1") (pintype "passive"))
    )
    (net (code "65") (name "Net-(IC8A-A3)") (class "Default")
      (node (ref "IC8") (pin "6") (pinfunction "A3_6") (pintype "input"))
      (node (ref "X") (pin "1") (pinfunction "1_1") (pintype "passive"))
    )
    (net (code "66") (name "Net-(IC8A-A4)") (class "Default")
      (node (ref "C") (pin "1") (pinfunction "1_1") (pintype "passive"))
      (node (ref "IC8") (pin "10") (pinfunction "A4_10") (pintype "input"))
    )
    (net (code "67") (name "Net-(IC8A-A5)") (class "Default")
      (node (ref "IC8") (pin "12") (pinfunction "A5_12") (pintype "input"))
      (node (ref "V") (pin "1") (pinfunction "1_1") (pintype "passive"))
    )
    (net (code "68") (name "Net-(IC8A-Y1)") (class "Default")
      (node (ref "D6") (pin "C") (pinfunction "C_C") (pintype "passive"))
      (node (ref "IC8") (pin "3") (pinfunction "Y1_3") (pintype "tri_state"))
    )
    (net (code "69") (name "Net-(IC8A-Y2)") (class "Default")
      (node (ref "D7") (pin "C") (pinfunction "C_C") (pintype "passive"))
      (node (ref "IC8") (pin "5") (pinfunction "Y2_5") (pintype "tri_state"))
    )
    (net (code "70") (name "Net-(IC8A-Y3)") (class "Default")
      (node (ref "D8") (pin "C") (pinfunction "C_C") (pintype "passive"))
      (node (ref "IC8") (pin "7") (pinfunction "Y3_7") (pintype "tri_state"))
    )
    (net (code "71") (name "Net-(IC8A-Y4)") (class "Default")
      (node (ref "D9") (pin "C") (pinfunction "C_C") (pintype "passive"))
      (node (ref "IC8") (pin "9") (pinfunction "Y4_9") (pintype "tri_state"))
    )
    (net (code "72") (name "Net-(IC8A-Y5)") (class "Default")
      (node (ref "D10") (pin "C") (pinfunction "C_C") (pintype "passive"))
      (node (ref "IC8") (pin "11") (pinfunction "Y5_11") (pintype "tri_state"))
    )
    (net (code "73") (name "Net-(IC9A-A1)") (class "Default")
      (node (ref "ENT") (pin "1") (pinfunction "1_1") (pintype "passive"))
      (node (ref "IC9") (pin "2") (pinfunction "A1_2") (pintype "input"))
    )
    (net (code "74") (name "Net-(IC9A-A2)") (class "Default")
      (node (ref "IC9") (pin "4") (pinfunction "A2_4") (pintype "input"))
      (node (ref "L") (pin "1") (pinfunction "1_1") (pintype "passive"))
    )
    (net (code "75") (name "Net-(IC9A-A3)") (class "Default")
      (node (ref "IC9") (pin "6") (pinfunction "A3_6") (pintype "input"))
      (node (ref "K") (pin "1") (pinfunction "1_1") (pintype "passive"))
    )
    (net (code "76") (name "Net-(IC9A-A4)") (class "Default")
      (node (ref "IC9") (pin "10") (pinfunction "A4_10") (pintype "input"))
      (node (ref "J") (pin "1") (pinfunction "1_1") (pintype "passive"))
    )
    (net (code "77") (name "Net-(IC9A-A5)") (class "Default")
      (node (ref "H") (pin "1") (pinfunction "1_1") (pintype "passive"))
      (node (ref "IC9") (pin "12") (pinfunction "A5_12") (pintype "input"))
    )
    (net (code "78") (name "Net-(IC9A-Y1)") (class "Default")
      (node (ref "D11") (pin "C") (pinfunction "C_C") (pintype "passive"))
      (node (ref "IC9") (pin "3") (pinfunction "Y1_3") (pintype "tri_state"))
    )
    (net (code "79") (name "Net-(IC9A-Y2)") (class "Default")
      (node (ref "D12") (pin "C") (pinfunction "C_C") (pintype "passive"))
      (node (ref "IC9") (pin "5") (pinfunction "Y2_5") (pintype "tri_state"))
    )
    (net (code "80") (name "Net-(IC9A-Y3)") (class "Default")
      (node (ref "D13") (pin "C") (pinfunction "C_C") (pintype "passive"))
      (node (ref "IC9") (pin "7") (pinfunction "Y3_7") (pintype "tri_state"))
    )
    (net (code "81") (name "Net-(IC9A-Y4)") (class "Default")
      (node (ref "D14") (pin "C") (pinfunction "C_C") (pintype "passive"))
      (node (ref "IC9") (pin "9") (pinfunction "Y4_9") (pintype "tri_state"))
    )
    (net (code "82") (name "Net-(IC9A-Y5)") (class "Default")
      (node (ref "D15") (pin "C") (pinfunction "C_C") (pintype "passive"))
      (node (ref "IC9") (pin "11") (pinfunction "Y5_11") (pintype "tri_state"))
    )
    (net (code "83") (name "Net-(IC10A-A1)") (class "Default")
      (node (ref "A") (pin "1") (pinfunction "1_1") (pintype "passive"))
      (node (ref "IC10") (pin "2") (pinfunction "A1_2") (pintype "input"))
    )
    (net (code "84") (name "Net-(IC10A-A2)") (class "Default")
      (node (ref "IC10") (pin "4") (pinfunction "A2_4") (pintype "input"))
      (node (ref "S") (pin "1") (pinfunction "1_1") (pintype "passive"))
    )
    (net (code "85") (name "Net-(IC10A-A3)") (class "Default")
      (node (ref "D") (pin "1") (pinfunction "1_1") (pintype "passive"))
      (node (ref "IC10") (pin "6") (pinfunction "A3_6") (pintype "input"))
    )
    (net (code "86") (name "Net-(IC10A-A4)") (class "Default")
      (node (ref "F") (pin "1") (pinfunction "1_1") (pintype "passive"))
      (node (ref "IC10") (pin "10") (pinfunction "A4_10") (pintype "input"))
    )
    (net (code "87") (name "Net-(IC10A-A5)") (class "Default")
      (node (ref "G") (pin "1") (pinfunction "1_1") (pintype "passive"))
      (node (ref "IC10") (pin "12") (pinfunction "A5_12") (pintype "input"))
    )
    (net (code "88") (name "Net-(IC10A-Y1)") (class "Default")
      (node (ref "D16") (pin "C") (pinfunction "C_C") (pintype "passive"))
      (node (ref "IC10") (pin "3") (pinfunction "Y1_3") (pintype "tri_state"))
    )
    (net (code "89") (name "Net-(IC10A-Y2)") (class "Default")
      (node (ref "D17") (pin "C") (pinfunction "C_C") (pintype "passive"))
      (node (ref "IC10") (pin "5") (pinfunction "Y2_5") (pintype "tri_state"))
    )
    (net (code "90") (name "Net-(IC10A-Y3)") (class "Default")
      (node (ref "D18") (pin "C") (pinfunction "C_C") (pintype "passive"))
      (node (ref "IC10") (pin "7") (pinfunction "Y3_7") (pintype "tri_state"))
    )
    (net (code "91") (name "Net-(IC10A-Y4)") (class "Default")
      (node (ref "D19") (pin "C") (pinfunction "C_C") (pintype "passive"))
      (node (ref "IC10") (pin "9") (pinfunction "Y4_9") (pintype "tri_state"))
    )
    (net (code "92") (name "Net-(IC10A-Y5)") (class "Default")
      (node (ref "D20") (pin "C") (pinfunction "C_C") (pintype "passive"))
      (node (ref "IC10") (pin "11") (pinfunction "Y5_11") (pintype "tri_state"))
    )
    (net (code "93") (name "Net-(IC11A-A1)") (class "Default")
      (node (ref "IC11") (pin "2") (pinfunction "A1_2") (pintype "input"))
      (node (ref "P") (pin "1") (pinfunction "1_1") (pintype "passive"))
    )
    (net (code "94") (name "Net-(IC11A-A2)") (class "Default")
      (node (ref "IC11") (pin "4") (pinfunction "A2_4") (pintype "input"))
      (node (ref "O") (pin "1") (pinfunction "1_1") (pintype "passive"))
    )
    (net (code "95") (name "Net-(IC11A-A3)") (class "Default")
      (node (ref "I") (pin "1") (pinfunction "1_1") (pintype "passive"))
      (node (ref "IC11") (pin "6") (pinfunction "A3_6") (pintype "input"))
    )
    (net (code "96") (name "Net-(IC11A-A4)") (class "Default")
      (node (ref "IC11") (pin "10") (pinfunction "A4_10") (pintype "input"))
      (node (ref "U") (pin "1") (pinfunction "1_1") (pintype "passive"))
    )
    (net (code "97") (name "Net-(IC11A-A5)") (class "Default")
      (node (ref "IC11") (pin "12") (pinfunction "A5_12") (pintype "input"))
      (node (ref "Y") (pin "1") (pinfunction "1_1") (pintype "passive"))
    )
    (net (code "98") (name "Net-(IC11A-Y1)") (class "Default")
      (node (ref "D21") (pin "C") (pinfunction "C_C") (pintype "passive"))
      (node (ref "IC11") (pin "3") (pinfunction "Y1_3") (pintype "tri_state"))
    )
    (net (code "99") (name "Net-(IC11A-Y2)") (class "Default")
      (node (ref "D22") (pin "C") (pinfunction "C_C") (pintype "passive"))
      (node (ref "IC11") (pin "5") (pinfunction "Y2_5") (pintype "tri_state"))
    )
    (net (code "100") (name "Net-(IC11A-Y3)") (class "Default")
      (node (ref "D23") (pin "C") (pinfunction "C_C") (pintype "passive"))
      (node (ref "IC11") (pin "7") (pinfunction "Y3_7") (pintype "tri_state"))
    )
    (net (code "101") (name "Net-(IC11A-Y4)") (class "Default")
      (node (ref "D24") (pin "C") (pinfunction "C_C") (pintype "passive"))
      (node (ref "IC11") (pin "9") (pinfunction "Y4_9") (pintype "tri_state"))
    )
    (net (code "102") (name "Net-(IC11A-Y5)") (class "Default")
      (node (ref "D25") (pin "C") (pinfunction "C_C") (pintype "passive"))
      (node (ref "IC11") (pin "11") (pinfunction "Y5_11") (pintype "tri_state"))
    )
    (net (code "103") (name "Net-(IC12A-A1)") (class "Default")
      (node (ref "IC12") (pin "2") (pinfunction "A1_2") (pintype "input"))
      (node (ref "Q") (pin "1") (pinfunction "1_1") (pintype "passive"))
    )
    (net (code "104") (name "Net-(IC12A-A2)") (class "Default")
      (node (ref "IC12") (pin "4") (pinfunction "A2_4") (pintype "input"))
      (node (ref "W") (pin "1") (pinfunction "1_1") (pintype "passive"))
    )
    (net (code "105") (name "Net-(IC12A-A3)") (class "Default")
      (node (ref "E") (pin "1") (pinfunction "1_1") (pintype "passive"))
      (node (ref "IC12") (pin "6") (pinfunction "A3_6") (pintype "input"))
    )
    (net (code "106") (name "Net-(IC12A-A4)") (class "Default")
      (node (ref "IC12") (pin "10") (pinfunction "A4_10") (pintype "input"))
      (node (ref "R") (pin "1") (pinfunction "1_1") (pintype "passive"))
    )
    (net (code "107") (name "Net-(IC12A-A5)") (class "Default")
      (node (ref "IC12") (pin "12") (pinfunction "A5_12") (pintype "input"))
      (node (ref "T") (pin "1") (pinfunction "1_1") (pintype "passive"))
    )
    (net (code "108") (name "Net-(IC12A-Y1)") (class "Default")
      (node (ref "D26") (pin "C") (pinfunction "C_C") (pintype "passive"))
      (node (ref "IC12") (pin "3") (pinfunction "Y1_3") (pintype "tri_state"))
    )
    (net (code "109") (name "Net-(IC12A-Y2)") (class "Default")
      (node (ref "D27") (pin "C") (pinfunction "C_C") (pintype "passive"))
      (node (ref "IC12") (pin "5") (pinfunction "Y2_5") (pintype "tri_state"))
    )
    (net (code "110") (name "Net-(IC12A-Y3)") (class "Default")
      (node (ref "D28") (pin "C") (pinfunction "C_C") (pintype "passive"))
      (node (ref "IC12") (pin "7") (pinfunction "Y3_7") (pintype "tri_state"))
    )
    (net (code "111") (name "Net-(IC12A-Y4)") (class "Default")
      (node (ref "D29") (pin "C") (pinfunction "C_C") (pintype "passive"))
      (node (ref "IC12") (pin "9") (pinfunction "Y4_9") (pintype "tri_state"))
    )
    (net (code "112") (name "Net-(IC12A-Y5)") (class "Default")
      (node (ref "D30") (pin "C") (pinfunction "C_C") (pintype "passive"))
      (node (ref "IC12") (pin "11") (pinfunction "Y5_11") (pintype "tri_state"))
    )
    (net (code "113") (name "Net-(IC13A-A1)") (class "Default")
      (node (ref "0") (pin "1") (pinfunction "1_1") (pintype "passive"))
      (node (ref "IC13") (pin "2") (pinfunction "A1_2") (pintype "input"))
    )
    (net (code "114") (name "Net-(IC13A-A2)") (class "Default")
      (node (ref "9") (pin "1") (pinfunction "1_1") (pintype "passive"))
      (node (ref "IC13") (pin "4") (pinfunction "A2_4") (pintype "input"))
    )
    (net (code "115") (name "Net-(IC13A-A3)") (class "Default")
      (node (ref "8") (pin "1") (pinfunction "1_1") (pintype "passive"))
      (node (ref "IC13") (pin "6") (pinfunction "A3_6") (pintype "input"))
    )
    (net (code "116") (name "Net-(IC13A-A4)") (class "Default")
      (node (ref "7") (pin "1") (pinfunction "1_1") (pintype "passive"))
      (node (ref "IC13") (pin "10") (pinfunction "A4_10") (pintype "input"))
    )
    (net (code "117") (name "Net-(IC13A-A5)") (class "Default")
      (node (ref "6") (pin "1") (pinfunction "1_1") (pintype "passive"))
      (node (ref "IC13") (pin "12") (pinfunction "A5_12") (pintype "input"))
    )
    (net (code "118") (name "Net-(IC13A-Y1)") (class "Default")
      (node (ref "D31") (pin "C") (pinfunction "C_C") (pintype "passive"))
      (node (ref "IC13") (pin "3") (pinfunction "Y1_3") (pintype "tri_state"))
    )
    (net (code "119") (name "Net-(IC13A-Y2)") (class "Default")
      (node (ref "D32") (pin "C") (pinfunction "C_C") (pintype "passive"))
      (node (ref "IC13") (pin "5") (pinfunction "Y2_5") (pintype "tri_state"))
    )
    (net (code "120") (name "Net-(IC13A-Y3)") (class "Default")
      (node (ref "D33") (pin "C") (pinfunction "C_C") (pintype "passive"))
      (node (ref "IC13") (pin "7") (pinfunction "Y3_7") (pintype "tri_state"))
    )
    (net (code "121") (name "Net-(IC13A-Y4)") (class "Default")
      (node (ref "D34") (pin "C") (pinfunction "C_C") (pintype "passive"))
      (node (ref "IC13") (pin "9") (pinfunction "Y4_9") (pintype "tri_state"))
    )
    (net (code "122") (name "Net-(IC13A-Y5)") (class "Default")
      (node (ref "D35") (pin "C") (pinfunction "C_C") (pintype "passive"))
      (node (ref "IC13") (pin "11") (pinfunction "Y5_11") (pintype "tri_state"))
    )
    (net (code "123") (name "Net-(IC14A-A1)") (class "Default")
      (node (ref "1") (pin "1") (pinfunction "1_1") (pintype "passive"))
      (node (ref "IC14") (pin "2") (pinfunction "A1_2") (pintype "input"))
    )
    (net (code "124") (name "Net-(IC14A-A2)") (class "Default")
      (node (ref "2") (pin "1") (pinfunction "1_1") (pintype "passive"))
      (node (ref "IC14") (pin "4") (pinfunction "A2_4") (pintype "input"))
    )
    (net (code "125") (name "Net-(IC14A-A3)") (class "Default")
      (node (ref "3") (pin "1") (pinfunction "1_1") (pintype "passive"))
      (node (ref "IC14") (pin "6") (pinfunction "A3_6") (pintype "input"))
    )
    (net (code "126") (name "Net-(IC14A-A4)") (class "Default")
      (node (ref "4") (pin "1") (pinfunction "1_1") (pintype "passive"))
      (node (ref "IC14") (pin "10") (pinfunction "A4_10") (pintype "input"))
    )
    (net (code "127") (name "Net-(IC14A-A5)") (class "Default")
      (node (ref "5") (pin "1") (pinfunction "1_1") (pintype "passive"))
      (node (ref "IC14") (pin "12") (pinfunction "A5_12") (pintype "input"))
    )
    (net (code "128") (name "Net-(IC14A-Y1)") (class "Default")
      (node (ref "D36") (pin "C") (pinfunction "C_C") (pintype "passive"))
      (node (ref "IC14") (pin "3") (pinfunction "Y1_3") (pintype "tri_state"))
    )
    (net (code "129") (name "Net-(IC14A-Y2)") (class "Default")
      (node (ref "D37") (pin "C") (pinfunction "C_C") (pintype "passive"))
      (node (ref "IC14") (pin "5") (pinfunction "Y2_5") (pintype "tri_state"))
    )
    (net (code "130") (name "Net-(IC14A-Y3)") (class "Default")
      (node (ref "D38") (pin "C") (pinfunction "C_C") (pintype "passive"))
      (node (ref "IC14") (pin "7") (pinfunction "Y3_7") (pintype "tri_state"))
    )
    (net (code "131") (name "Net-(IC14A-Y4)") (class "Default")
      (node (ref "D39") (pin "C") (pinfunction "C_C") (pintype "passive"))
      (node (ref "IC14") (pin "9") (pinfunction "Y4_9") (pintype "tri_state"))
    )
    (net (code "132") (name "Net-(IC14A-Y5)") (class "Default")
      (node (ref "D40") (pin "C") (pinfunction "C_C") (pintype "passive"))
      (node (ref "IC14") (pin "11") (pinfunction "Y5_11") (pintype "tri_state"))
    )
    (net (code "133") (name "Net-(LEFTJ1-Pad1)") (class "Default")
      (node (ref "LEFTJ1") (pin "1") (pinfunction "1_1") (pintype "passive"))
      (node (ref "X1") (pin "3") (pinfunction "3_3") (pintype "passive"))
    )
    (net (code "134") (name "Net-(LEFTJ2-Pad1)") (class "Default")
      (node (ref "LEFTJ2") (pin "1") (pinfunction "1_1") (pintype "passive"))
      (node (ref "X2") (pin "3") (pinfunction "3_3") (pintype "passive"))
    )
    (net (code "135") (name "Net-(LEFTJ3-Pad1)") (class "Default")
      (node (ref "LEFTJ3") (pin "1") (pinfunction "1_1") (pintype "passive"))
      (node (ref "X3") (pin "3") (pinfunction "3_3") (pintype "passive"))
    )
    (net (code "136") (name "Net-(LEFTJ4-Pad1)") (class "Default")
      (node (ref "LEFTJ4") (pin "1") (pinfunction "1_1") (pintype "passive"))
      (node (ref "X4") (pin "3") (pinfunction "3_3") (pintype "passive"))
    )
    (net (code "137") (name "Net-(PIN5J1-Pad1)") (class "Default")
      (node (ref "PIN5J1") (pin "1") (pinfunction "1_1") (pintype "passive"))
      (node (ref "X1") (pin "1") (pinfunction "1_1") (pintype "passive"))
    )
    (net (code "138") (name "Net-(PIN5J2-Pad1)") (class "Default")
      (node (ref "PIN5J2") (pin "1") (pinfunction "1_1") (pintype "passive"))
      (node (ref "X2") (pin "1") (pinfunction "1_1") (pintype "passive"))
    )
    (net (code "139") (name "Net-(PIN5J3-Pad1)") (class "Default")
      (node (ref "PIN5J3") (pin "1") (pinfunction "1_1") (pintype "passive"))
      (node (ref "X3") (pin "1") (pinfunction "1_1") (pintype "passive"))
    )
    (net (code "140") (name "Net-(PIN5J4-Pad1)") (class "Default")
      (node (ref "PIN5J4") (pin "1") (pinfunction "1_1") (pintype "passive"))
      (node (ref "X4") (pin "1") (pinfunction "1_1") (pintype "passive"))
    )
    (net (code "141") (name "Net-(PIN7J1-Pad1)") (class "Default")
      (node (ref "PIN7J1") (pin "1") (pinfunction "1_1") (pintype "passive"))
      (node (ref "X1") (pin "8") (pinfunction "8_8") (pintype "passive"))
    )
    (net (code "142") (name "Net-(PIN7J2-Pad1)") (class "Default")
      (node (ref "PIN7J2") (pin "1") (pinfunction "1_1") (pintype "passive"))
      (node (ref "X2") (pin "8") (pinfunction "8_8") (pintype "passive"))
    )
    (net (code "143") (name "Net-(PIN7J3-Pad1)") (class "Default")
      (node (ref "PIN7J3") (pin "1") (pinfunction "1_1") (pintype "passive"))
      (node (ref "X3") (pin "8") (pinfunction "8_8") (pintype "passive"))
    )
    (net (code "144") (name "Net-(PIN7J4-Pad1)") (class "Default")
      (node (ref "PIN7J4") (pin "1") (pinfunction "1_1") (pintype "passive"))
      (node (ref "X4") (pin "8") (pinfunction "8_8") (pintype "passive"))
    )
    (net (code "145") (name "Net-(PIN9J1-Pad1)") (class "Default")
      (node (ref "PIN9J1") (pin "1") (pinfunction "1_1") (pintype "passive"))
      (node (ref "X1") (pin "6") (pinfunction "6_6") (pintype "passive"))
    )
    (net (code "146") (name "Net-(PIN9J2-Pad1)") (class "Default")
      (node (ref "PIN9J2") (pin "1") (pinfunction "1_1") (pintype "passive"))
      (node (ref "X2") (pin "6") (pinfunction "6_6") (pintype "passive"))
    )
    (net (code "147") (name "Net-(PIN9J3-Pad1)") (class "Default")
      (node (ref "PIN9J3") (pin "1") (pinfunction "1_1") (pintype "passive"))
      (node (ref "X3") (pin "6") (pinfunction "6_6") (pintype "passive"))
    )
    (net (code "148") (name "Net-(PIN9J4-Pad1)") (class "Default")
      (node (ref "PIN9J4") (pin "1") (pinfunction "1_1") (pintype "passive"))
      (node (ref "X4") (pin "6") (pinfunction "6_6") (pintype "passive"))
    )
    (net (code "149") (name "Net-(RIGHTJ1-Pad1)") (class "Default")
      (node (ref "RIGHTJ1") (pin "1") (pinfunction "1_1") (pintype "passive"))
      (node (ref "X1") (pin "2") (pinfunction "2_2") (pintype "passive"))
    )
    (net (code "150") (name "Net-(RIGHTJ2-Pad1)") (class "Default")
      (node (ref "RIGHTJ2") (pin "1") (pinfunction "1_1") (pintype "passive"))
      (node (ref "X2") (pin "2") (pinfunction "2_2") (pintype "passive"))
    )
    (net (code "151") (name "Net-(RIGHTJ3-Pad1)") (class "Default")
      (node (ref "RIGHTJ3") (pin "1") (pinfunction "1_1") (pintype "passive"))
      (node (ref "X3") (pin "2") (pinfunction "2_2") (pintype "passive"))
    )
    (net (code "152") (name "Net-(RIGHTJ4-Pad1)") (class "Default")
      (node (ref "RIGHTJ4") (pin "1") (pinfunction "1_1") (pintype "passive"))
      (node (ref "X4") (pin "2") (pinfunction "2_2") (pintype "passive"))
    )
    (net (code "153") (name "Net-(UPJ1-Pad1)") (class "Default")
      (node (ref "UPJ1") (pin "1") (pinfunction "1_1") (pintype "passive"))
      (node (ref "X1") (pin "5") (pinfunction "5_5") (pintype "passive"))
    )
    (net (code "154") (name "Net-(UPJ2-Pad1)") (class "Default")
      (node (ref "UPJ2") (pin "1") (pinfunction "1_1") (pintype "passive"))
      (node (ref "X2") (pin "5") (pinfunction "5_5") (pintype "passive"))
    )
    (net (code "155") (name "Net-(UPJ3-Pad1)") (class "Default")
      (node (ref "UPJ3") (pin "1") (pinfunction "1_1") (pintype "passive"))
      (node (ref "X3") (pin "5") (pinfunction "5_5") (pintype "passive"))
    )
    (net (code "156") (name "Net-(UPJ4-Pad1)") (class "Default")
      (node (ref "UPJ4") (pin "1") (pinfunction "1_1") (pintype "passive"))
      (node (ref "X4") (pin "5") (pinfunction "5_5") (pintype "passive"))
    )
    (net (code "157") (name "VCC") (class "Default")
      (node (ref "C1") (pin "1") (pinfunction "1_1") (pintype "passive"))
      (node (ref "C10") (pin "1") (pinfunction "1_1") (pintype "passive"))
      (node (ref "C2") (pin "1") (pinfunction "1_1") (pintype "passive"))
      (node (ref "C3") (pin "1") (pinfunction "1_1") (pintype "passive"))
      (node (ref "C4") (pin "1") (pinfunction "1_1") (pintype "passive"))
      (node (ref "C5") (pin "1") (pinfunction "1_1") (pintype "passive"))
      (node (ref "C6") (pin "1") (pinfunction "1_1") (pintype "passive"))
      (node (ref "C7") (pin "1") (pinfunction "1_1") (pintype "passive"))
      (node (ref "C8") (pin "1") (pinfunction "1_1") (pintype "passive"))
      (node (ref "C9") (pin "1") (pinfunction "1_1") (pintype "passive"))
      (node (ref "IC2") (pin "14") (pinfunction "A6_14") (pintype "input"))
      (node (ref "U$1") (pin "+5V") (pinfunction "+5V_+5V") (pintype "bidirectional"))
      (node (ref "U$3") (pin "A3") (pinfunction "5V_A3") (pintype "power_in"))
      (node (ref "VCCJ1") (pin "1") (pinfunction "1_1") (pintype "passive"))
      (node (ref "VCCJ2") (pin "1") (pinfunction "1_1") (pintype "passive"))
    )
    (net (code "158") (name "unconnected-(IC7A-A6-Pad14)") (class "Default")
      (node (ref "IC7") (pin "14") (pinfunction "A6_14") (pintype "input"))
    )
    (net (code "159") (name "unconnected-(IC7A-Y6-Pad13)") (class "Default")
      (node (ref "IC7") (pin "13") (pinfunction "Y6_13") (pintype "tri_state"))
    )
    (net (code "160") (name "unconnected-(IC8A-A6-Pad14)") (class "Default")
      (node (ref "IC8") (pin "14") (pinfunction "A6_14") (pintype "input"))
    )
    (net (code "161") (name "unconnected-(IC8A-Y6-Pad13)") (class "Default")
      (node (ref "IC8") (pin "13") (pinfunction "Y6_13") (pintype "tri_state"))
    )
    (net (code "162") (name "unconnected-(IC9A-A6-Pad14)") (class "Default")
      (node (ref "IC9") (pin "14") (pinfunction "A6_14") (pintype "input"))
    )
    (net (code "163") (name "unconnected-(IC9A-Y6-Pad13)") (class "Default")
      (node (ref "IC9") (pin "13") (pinfunction "Y6_13") (pintype "tri_state"))
    )
    (net (code "164") (name "unconnected-(IC10A-A6-Pad14)") (class "Default")
      (node (ref "IC10") (pin "14") (pinfunction "A6_14") (pintype "input"))
    )
    (net (code "165") (name "unconnected-(IC10A-Y6-Pad13)") (class "Default")
      (node (ref "IC10") (pin "13") (pinfunction "Y6_13") (pintype "tri_state"))
    )
    (net (code "166") (name "unconnected-(IC11A-A6-Pad14)") (class "Default")
      (node (ref "IC11") (pin "14") (pinfunction "A6_14") (pintype "input"))
    )
    (net (code "167") (name "unconnected-(IC11A-Y6-Pad13)") (class "Default")
      (node (ref "IC11") (pin "13") (pinfunction "Y6_13") (pintype "tri_state"))
    )
    (net (code "168") (name "unconnected-(IC12A-A6-Pad14)") (class "Default")
      (node (ref "IC12") (pin "14") (pinfunction "A6_14") (pintype "input"))
    )
    (net (code "169") (name "unconnected-(IC12A-Y6-Pad13)") (class "Default")
      (node (ref "IC12") (pin "13") (pinfunction "Y6_13") (pintype "tri_state"))
    )
    (net (code "170") (name "unconnected-(IC13A-A6-Pad14)") (class "Default")
      (node (ref "IC13") (pin "14") (pinfunction "A6_14") (pintype "input"))
    )
    (net (code "171") (name "unconnected-(IC13A-Y6-Pad13)") (class "Default")
      (node (ref "IC13") (pin "13") (pinfunction "Y6_13") (pintype "tri_state"))
    )
    (net (code "172") (name "unconnected-(IC14A-A6-Pad14)") (class "Default")
      (node (ref "IC14") (pin "14") (pinfunction "A6_14") (pintype "input"))
    )
    (net (code "173") (name "unconnected-(IC14A-Y6-Pad13)") (class "Default")
      (node (ref "IC14") (pin "13") (pinfunction "Y6_13") (pintype "tri_state"))
    )
    (net (code "174") (name "unconnected-(U$3-CK-PadA8)") (class "Default")
      (node (ref "U$3") (pin "A8") (pinfunction "CK_A8") (pintype "bidirectional"))
    )
    (net (code "175") (name "unconnected-(U$3-NC-PadB4)") (class "Default")
      (node (ref "U$3") (pin "B4") (pinfunction "NC_B4") (pintype "no_connect"))
    )
    (net (code "176") (name "unconnected-(U$3-NC2-PadB28)") (class "Default")
      (node (ref "U$3") (pin "B28") (pinfunction "NC2_B28") (pintype "no_connect"))
    )
    (net (code "177") (name "unconnected-(U$3-U-PadA18)") (class "Default")
      (node (ref "U$3") (pin "A18") (pinfunction "U_A18") (pintype "bidirectional"))
    )
    (net (code "178") (name "unconnected-(U$3-V-PadA17)") (class "Default")
      (node (ref "U$3") (pin "A17") (pinfunction "V_A17") (pintype "bidirectional"))
    )
    (net (code "179") (name "unconnected-(U$3-VIDEO-PadA15)") (class "Default")
      (node (ref "U$3") (pin "A15") (pinfunction "VIDEO_A15") (pintype "bidirectional"))
    )
    (net (code "180") (name "unconnected-(U$3-{slash}BUSACK-PadA26)") (class "Default")
      (node (ref "U$3") (pin "A26") (pinfunction "/BUSACK_A26") (pintype "bidirectional"))
    )
    (net (code "181") (name "unconnected-(U$3-{slash}BUSRQ-PadA19)") (class "Default")
      (node (ref "U$3") (pin "A19") (pinfunction "/BUSRQ_A19") (pintype "bidirectional"))
    )
    (net (code "182") (name "unconnected-(U$3-{slash}HALT-PadB15)") (class "Default")
      (node (ref "U$3") (pin "B15") (pinfunction "/HALT_B15") (pintype "bidirectional"))
    )
    (net (code "183") (name "unconnected-(U$3-{slash}INT-PadB13)") (class "Default")
      (node (ref "U$3") (pin "B13") (pinfunction "/INT_B13") (pintype "bidirectional"))
    )
    (net (code "184") (name "unconnected-(U$3-{slash}IORQ_ULA-PadA13)") (class "Default")
      (node (ref "U$3") (pin "A13") (pinfunction "/IORQ_ULA_A13") (pintype "bidirectional"))
    )
    (net (code "185") (name "unconnected-(U$3-{slash}M1-PadB24)") (class "Default")
      (node (ref "U$3") (pin "B24") (pinfunction "/M1_B24") (pintype "bidirectional"))
    )
    (net (code "186") (name "unconnected-(U$3-{slash}NMI-PadB14)") (class "Default")
      (node (ref "U$3") (pin "B14") (pinfunction "/NMI_B14") (pintype "bidirectional"))
    )
    (net (code "187") (name "unconnected-(U$3-{slash}RESET-PadA20)") (class "Default")
      (node (ref "U$3") (pin "A20") (pinfunction "/RESET_A20") (pintype "bidirectional"))
    )
    (net (code "188") (name "unconnected-(U$3-{slash}RFSH-PadB25)") (class "Default")
      (node (ref "U$3") (pin "B25") (pinfunction "/RFSH_B25") (pintype "bidirectional"))
    )
    (net (code "189") (name "unconnected-(U$3-{slash}WAIT-PadB21)") (class "Default")
      (node (ref "U$3") (pin "B21") (pinfunction "/WAIT_B21") (pintype "bidirectional"))
    )
    (net (code "190") (name "unconnected-(U$3-{slash}Y-PadA16)") (class "Default")
      (node (ref "U$3") (pin "A16") (pinfunction "/Y_A16") (pintype "bidirectional"))
    )
  )
)
